# with_usb.net
KiCad netlist of a schematic drawn in EAGLE
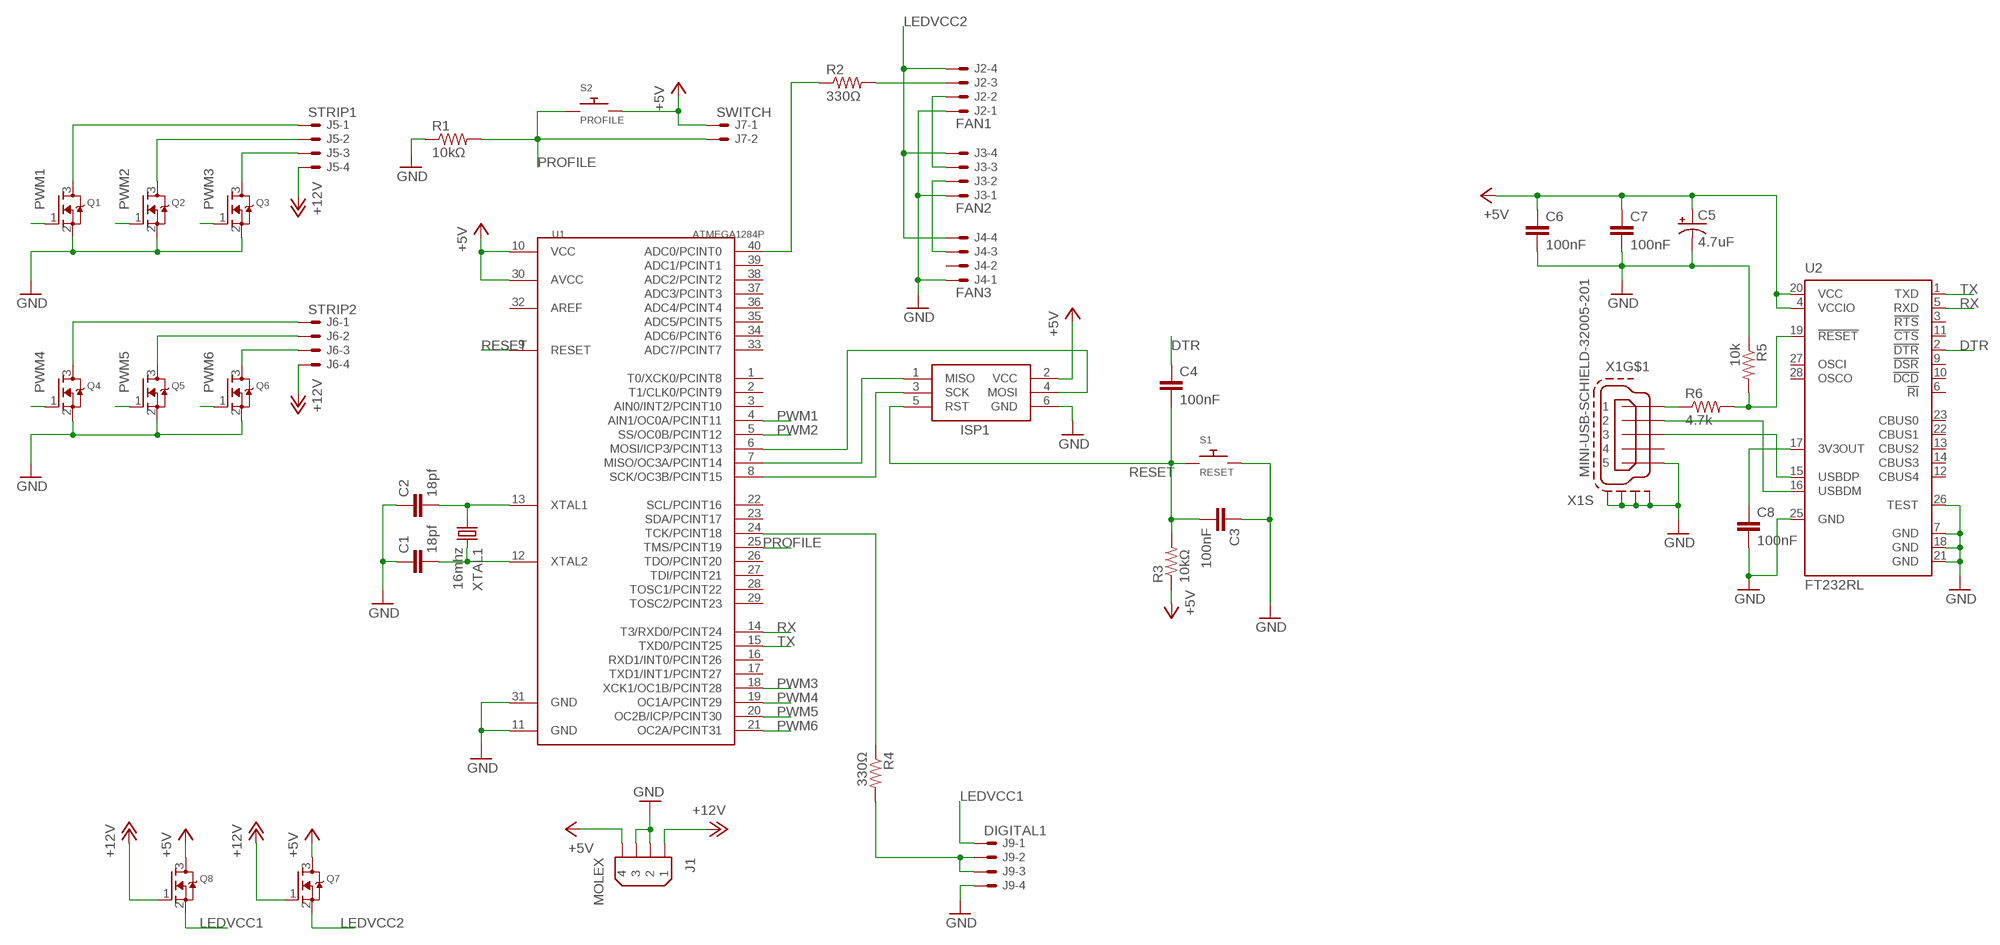
[diagram p0: schematic, sheet 1]

(export (version "E")
  (design (tool "Eeschema 10.0.6"))
  (components
    (comp (ref "C1")
      (value "18pf")
      (footprint "eagle-import:C0805")
      (libsource (lib "eagle-import") (part "C"))
    )
    (comp (ref "C2")
      (value "18pf")
      (footprint "eagle-import:C0805")
      (libsource (lib "eagle-import") (part "C"))
    )
    (comp (ref "C3")
      (value "100nF")
      (footprint "eagle-import:C0805")
      (libsource (lib "eagle-import") (part "C-EUC0805"))
    )
    (comp (ref "C4")
      (value "100nF")
      (footprint "eagle-import:C0805")
      (libsource (lib "eagle-import") (part "C-EUC0805"))
    )
    (comp (ref "C5")
      (value "4.7uF")
      (footprint "eagle-import:153CLV-0505")
      (libsource (lib "eagle-import") (part "CPOL-US153CLV-0505"))
    )
    (comp (ref "C6")
      (value "100nF")
      (footprint "eagle-import:C0805")
      (libsource (lib "eagle-import") (part "resistor_348_C-EUC0805"))
    )
    (comp (ref "C7")
      (value "100nF")
      (footprint "eagle-import:C0805")
      (libsource (lib "eagle-import") (part "resistor_348_C-EUC0805"))
    )
    (comp (ref "C8")
      (value "100nF")
      (footprint "eagle-import:C0805")
      (libsource (lib "eagle-import") (part "resistor_348_C-EUC0805"))
    )
    (comp (ref "ISP1")
      (value "AVRISP-6")
      (footprint "eagle-import:AVRISP")
      (libsource (lib "eagle-import") (part "AVRISP-6"))
    )
    (comp (ref "J1")
      (value "MOLEX")
      (footprint "eagle-import:9090-4R")
      (libsource (lib "eagle-import") (part "9090-4R"))
    )
    (comp (ref "J2")
      (value "FAN1")
      (footprint "eagle-import:22-23-2041")
      (fields (field (name "MF") "MOLEX") (field (name "MPN") "22-23-2041"))
      (libsource (lib "eagle-import") (part "22-23-2041"))
    )
    (comp (ref "J3")
      (value "FAN2")
      (footprint "eagle-import:22-23-2041")
      (fields (field (name "MF") "MOLEX") (field (name "MPN") "22-23-2041"))
      (libsource (lib "eagle-import") (part "22-23-2041"))
    )
    (comp (ref "J4")
      (value "FAN3")
      (footprint "eagle-import:22-23-2041")
      (fields (field (name "MF") "MOLEX") (field (name "MPN") "22-23-2041"))
      (libsource (lib "eagle-import") (part "22-23-2041"))
    )
    (comp (ref "J5")
      (value "STRIP1")
      (footprint "eagle-import:22-23-2041")
      (fields (field (name "MF") "MOLEX") (field (name "MPN") "22-23-2041"))
      (libsource (lib "eagle-import") (part "22-23-2041"))
    )
    (comp (ref "J6")
      (value "STRIP2")
      (footprint "eagle-import:22-23-2041")
      (fields (field (name "MF") "MOLEX") (field (name "MPN") "22-23-2041"))
      (libsource (lib "eagle-import") (part "22-23-2041"))
    )
    (comp (ref "J7")
      (value "SWITCH")
      (footprint "eagle-import:22-23-2021")
      (fields (field (name "MF") "MOLEX") (field (name "MPN") "22-23-2021"))
      (libsource (lib "eagle-import") (part "22-23-2021"))
    )
    (comp (ref "J9")
      (value "DIGITAL1")
      (footprint "eagle-import:22-23-2041")
      (fields (field (name "MF") "MOLEX") (field (name "MPN") "22-23-2041"))
      (libsource (lib "eagle-import") (part "22-23-2041"))
    )
    (comp (ref "Q1")
      (value "MOSFET-NREFLOW")
      (footprint "eagle-import:SOT23")
      (libsource (lib "eagle-import") (part "MOSFET-NREFLOW"))
    )
    (comp (ref "Q2")
      (value "MOSFET-NREFLOW")
      (footprint "eagle-import:SOT23")
      (libsource (lib "eagle-import") (part "MOSFET-NREFLOW"))
    )
    (comp (ref "Q3")
      (value "MOSFET-NREFLOW")
      (footprint "eagle-import:SOT23")
      (libsource (lib "eagle-import") (part "MOSFET-NREFLOW"))
    )
    (comp (ref "Q4")
      (value "MOSFET-NREFLOW")
      (footprint "eagle-import:SOT23")
      (libsource (lib "eagle-import") (part "MOSFET-NREFLOW"))
    )
    (comp (ref "Q5")
      (value "MOSFET-NREFLOW")
      (footprint "eagle-import:SOT23")
      (libsource (lib "eagle-import") (part "MOSFET-NREFLOW"))
    )
    (comp (ref "Q6")
      (value "MOSFET-NREFLOW")
      (footprint "eagle-import:SOT23")
      (libsource (lib "eagle-import") (part "MOSFET-NREFLOW"))
    )
    (comp (ref "Q7")
      (value "MOSFET-NREFLOW")
      (footprint "eagle-import:SOT23")
      (libsource (lib "eagle-import") (part "MOSFET-NREFLOW"))
    )
    (comp (ref "Q8")
      (value "MOSFET-NREFLOW")
      (footprint "eagle-import:SOT23")
      (libsource (lib "eagle-import") (part "MOSFET-NREFLOW"))
    )
    (comp (ref "R1")
      (value "10kΩ")
      (footprint "eagle-import:M0805")
      (libsource (lib "eagle-import") (part "R-US_M0805"))
    )
    (comp (ref "R2")
      (value "330Ω")
      (footprint "eagle-import:M0805")
      (libsource (lib "eagle-import") (part "R-US_M0805"))
    )
    (comp (ref "R3")
      (value "10kΩ")
      (footprint "eagle-import:M0805")
      (libsource (lib "eagle-import") (part "R-US_M0805"))
    )
    (comp (ref "R4")
      (value "330Ω")
      (footprint "eagle-import:M0805")
      (libsource (lib "eagle-import") (part "R-US_M0805"))
    )
    (comp (ref "R5")
      (value "10k")
      (footprint "eagle-import:R0805")
      (libsource (lib "eagle-import") (part "resistor_348_R-US_R0805"))
    )
    (comp (ref "R6")
      (value "4.7k")
      (footprint "eagle-import:R0805")
      (libsource (lib "eagle-import") (part "resistor_348_R-US_R0805"))
    )
    (comp (ref "S1")
      (value "RESET")
      (footprint "eagle-import:B3F-1000")
      (libsource (lib "eagle-import") (part "BUTTON"))
    )
    (comp (ref "S2")
      (value "PROFILE")
      (footprint "eagle-import:B3F-1000")
      (libsource (lib "eagle-import") (part "BUTTON"))
    )
    (comp (ref "U1")
      (value "ATMEGA1284P")
      (footprint "eagle-import:DIL40")
      (libsource (lib "eagle-import") (part "MEGA1284P"))
    )
    (comp (ref "U2")
      (value "FT232RL")
      (footprint "eagle-import:SSOP28")
      (libsource (lib "eagle-import") (part "FT232RL"))
    )
    (comp (ref "X1")
      (value "MINI-USB-SCHIELD-32005-201")
      (footprint "eagle-import:32005-201")
      (libsource (lib "eagle-import") (part "MINI-USB-SCHIELD-32005-201"))
    )
    (comp (ref "XTAL1")
      (value "16mhz")
      (footprint "eagle-import:HC49U-V")
      (libsource (lib "eagle-import") (part "CRYSTALHC49U-V"))
    )
  )
  (nets
    (net (code "1") (name "+5V") (class "Default")
      (node (ref "C5") (pin "+") (pinfunction "+_+") (pintype "passive"))
      (node (ref "C6") (pin "1") (pinfunction "1_1") (pintype "passive"))
      (node (ref "C7") (pin "1") (pinfunction "1_1") (pintype "passive"))
      (node (ref "ISP1") (pin "2") (pinfunction "VCC_2") (pintype "power_in"))
      (node (ref "J1") (pin "4") (pinfunction "4_4") (pintype "passive"))
      (node (ref "J7") (pin "1") (pinfunction "S_1") (pintype "passive"))
      (node (ref "Q7") (pin "3") (pinfunction "D_3") (pintype "bidirectional"))
      (node (ref "Q8") (pin "3") (pinfunction "D_3") (pintype "bidirectional"))
      (node (ref "R3") (pin "1") (pinfunction "1_1") (pintype "passive"))
      (node (ref "S2") (pin "3") (pinfunction "P$2_3") (pintype "passive"))
      (node (ref "S2") (pin "4") (pinfunction "P$2_4") (pintype "passive"))
      (node (ref "U1") (pin "10") (pinfunction "VCC_10") (pintype "bidirectional"))
      (node (ref "U1") (pin "30") (pinfunction "AVCC_30") (pintype "bidirectional"))
      (node (ref "U2") (pin "20") (pinfunction "VCC_20") (pintype "power_in"))
      (node (ref "U2") (pin "4") (pinfunction "VCCIO_4") (pintype "power_in"))
    )
    (net (code "2") (name "+12V") (class "Default")
      (node (ref "J1") (pin "1") (pinfunction "1_1") (pintype "passive"))
      (node (ref "J5") (pin "4") (pinfunction "S_4") (pintype "passive"))
      (node (ref "J6") (pin "4") (pinfunction "S_4") (pintype "passive"))
      (node (ref "Q7") (pin "1") (pinfunction "G_1") (pintype "bidirectional"))
      (node (ref "Q8") (pin "1") (pinfunction "G_1") (pintype "bidirectional"))
    )
    (net (code "3") (name "/DTR") (class "Default")
      (node (ref "C4") (pin "1") (pinfunction "1_1") (pintype "passive"))
      (node (ref "U2") (pin "2") (pinfunction "~{DTR}_2") (pintype "output"))
    )
    (net (code "4") (name "/LEDVCC1") (class "Default")
      (node (ref "J9") (pin "1") (pinfunction "S_1") (pintype "passive"))
      (node (ref "Q8") (pin "2") (pinfunction "S_2") (pintype "bidirectional"))
    )
    (net (code "5") (name "/LEDVCC2") (class "Default")
      (node (ref "J2") (pin "4") (pinfunction "S_4") (pintype "passive"))
      (node (ref "J3") (pin "4") (pinfunction "S_4") (pintype "passive"))
      (node (ref "J4") (pin "4") (pinfunction "S_4") (pintype "passive"))
      (node (ref "Q7") (pin "2") (pinfunction "S_2") (pintype "bidirectional"))
    )
    (net (code "6") (name "/PROFILE") (class "Default")
      (node (ref "J7") (pin "2") (pinfunction "S_2") (pintype "passive"))
      (node (ref "R1") (pin "2") (pinfunction "2_2") (pintype "passive"))
      (node (ref "S2") (pin "1") (pinfunction "P$1_1") (pintype "passive"))
      (node (ref "S2") (pin "2") (pinfunction "P$1_2") (pintype "passive"))
      (node (ref "U1") (pin "25") (pinfunction "TMS/PCINT19_25") (pintype "bidirectional"))
    )
    (net (code "7") (name "/PWM1") (class "Default")
      (node (ref "Q1") (pin "1") (pinfunction "G_1") (pintype "bidirectional"))
      (node (ref "U1") (pin "4") (pinfunction "AIN1/OC0A/PCINT11_4") (pintype "bidirectional"))
    )
    (net (code "8") (name "/PWM2") (class "Default")
      (node (ref "Q2") (pin "1") (pinfunction "G_1") (pintype "bidirectional"))
      (node (ref "U1") (pin "5") (pinfunction "SS/OC0B/PCINT12_5") (pintype "bidirectional"))
    )
    (net (code "9") (name "/PWM3") (class "Default")
      (node (ref "Q3") (pin "1") (pinfunction "G_1") (pintype "bidirectional"))
      (node (ref "U1") (pin "18") (pinfunction "XCK1/OC1B/PCINT28_18") (pintype "bidirectional"))
    )
    (net (code "10") (name "/PWM4") (class "Default")
      (node (ref "Q4") (pin "1") (pinfunction "G_1") (pintype "bidirectional"))
      (node (ref "U1") (pin "19") (pinfunction "OC1A/PCINT29_19") (pintype "bidirectional"))
    )
    (net (code "11") (name "/PWM5") (class "Default")
      (node (ref "Q5") (pin "1") (pinfunction "G_1") (pintype "bidirectional"))
      (node (ref "U1") (pin "20") (pinfunction "OC2B/ICP/PCINT30_20") (pintype "bidirectional"))
    )
    (net (code "12") (name "/PWM6") (class "Default")
      (node (ref "Q6") (pin "1") (pinfunction "G_1") (pintype "bidirectional"))
      (node (ref "U1") (pin "21") (pinfunction "OC2A/PCINT31_21") (pintype "bidirectional"))
    )
    (net (code "13") (name "/RESET") (class "Default")
      (node (ref "C3") (pin "2") (pinfunction "2_2") (pintype "passive"))
      (node (ref "C4") (pin "2") (pinfunction "2_2") (pintype "passive"))
      (node (ref "ISP1") (pin "5") (pinfunction "RST_5") (pintype "output"))
      (node (ref "R3") (pin "2") (pinfunction "2_2") (pintype "passive"))
      (node (ref "S1") (pin "1") (pinfunction "P$1_1") (pintype "passive"))
      (node (ref "S1") (pin "2") (pinfunction "P$1_2") (pintype "passive"))
      (node (ref "U1") (pin "9") (pinfunction "RESET_9") (pintype "bidirectional"))
    )
    (net (code "14") (name "/RX") (class "Default")
      (node (ref "U1") (pin "14") (pinfunction "T3/RXD0/PCINT24_14") (pintype "bidirectional"))
      (node (ref "U2") (pin "5") (pinfunction "RXD_5") (pintype "input"))
    )
    (net (code "15") (name "/TX") (class "Default")
      (node (ref "U1") (pin "15") (pinfunction "TXD0/PCINT25_15") (pintype "bidirectional"))
      (node (ref "U2") (pin "1") (pinfunction "TXD_1") (pintype "output"))
    )
    (net (code "16") (name "GND") (class "Default")
      (node (ref "C1") (pin "1") (pinfunction "1_1") (pintype "passive"))
      (node (ref "C2") (pin "1") (pinfunction "1_1") (pintype "passive"))
      (node (ref "C3") (pin "1") (pinfunction "1_1") (pintype "passive"))
      (node (ref "C5") (pin "-") (pinfunction "-_-") (pintype "passive"))
      (node (ref "C6") (pin "2") (pinfunction "2_2") (pintype "passive"))
      (node (ref "C7") (pin "2") (pinfunction "2_2") (pintype "passive"))
      (node (ref "C8") (pin "2") (pinfunction "2_2") (pintype "passive"))
      (node (ref "ISP1") (pin "6") (pinfunction "GND_6") (pintype "power_in"))
      (node (ref "J1") (pin "2") (pinfunction "2_2") (pintype "passive"))
      (node (ref "J1") (pin "3") (pinfunction "3_3") (pintype "passive"))
      (node (ref "J2") (pin "1") (pinfunction "S_1") (pintype "passive"))
      (node (ref "J3") (pin "1") (pinfunction "S_1") (pintype "passive"))
      (node (ref "J4") (pin "1") (pinfunction "S_1") (pintype "passive"))
      (node (ref "J9") (pin "4") (pinfunction "S_4") (pintype "passive"))
      (node (ref "Q1") (pin "2") (pinfunction "S_2") (pintype "bidirectional"))
      (node (ref "Q2") (pin "2") (pinfunction "S_2") (pintype "bidirectional"))
      (node (ref "Q3") (pin "2") (pinfunction "S_2") (pintype "bidirectional"))
      (node (ref "Q4") (pin "2") (pinfunction "S_2") (pintype "bidirectional"))
      (node (ref "Q5") (pin "2") (pinfunction "S_2") (pintype "bidirectional"))
      (node (ref "Q6") (pin "2") (pinfunction "S_2") (pintype "bidirectional"))
      (node (ref "R1") (pin "1") (pinfunction "1_1") (pintype "passive"))
      (node (ref "R5") (pin "1") (pinfunction "1_1") (pintype "passive"))
      (node (ref "S1") (pin "3") (pinfunction "P$2_3") (pintype "passive"))
      (node (ref "S1") (pin "4") (pinfunction "P$2_4") (pintype "passive"))
      (node (ref "U1") (pin "11") (pinfunction "GND_11") (pintype "bidirectional"))
      (node (ref "U1") (pin "31") (pinfunction "GND_31") (pintype "bidirectional"))
      (node (ref "U2") (pin "18") (pinfunction "GND_18") (pintype "power_in"))
      (node (ref "U2") (pin "21") (pinfunction "GND_21") (pintype "power_in"))
      (node (ref "U2") (pin "25") (pinfunction "GND_25") (pintype "power_in"))
      (node (ref "U2") (pin "26") (pinfunction "TEST_26") (pintype "input"))
      (node (ref "U2") (pin "7") (pinfunction "GND_7") (pintype "power_in"))
      (node (ref "X1") (pin "5") (pinfunction "5_5") (pintype "passive"))
      (node (ref "X1") (pin "M1") (pinfunction "S1_M1") (pintype "passive"))
      (node (ref "X1") (pin "M2") (pinfunction "S2_M2") (pintype "passive"))
      (node (ref "X1") (pin "M3") (pinfunction "S3_M3") (pintype "passive"))
      (node (ref "X1") (pin "M4") (pinfunction "S4_M4") (pintype "passive"))
    )
    (net (code "17") (name "Net-(ISP1-MISO)") (class "Default")
      (node (ref "ISP1") (pin "1") (pinfunction "MISO_1") (pintype "input"))
      (node (ref "U1") (pin "7") (pinfunction "MISO/OC3A/PCINT14_7") (pintype "bidirectional"))
    )
    (net (code "18") (name "Net-(ISP1-MOSI)") (class "Default")
      (node (ref "ISP1") (pin "4") (pinfunction "MOSI_4") (pintype "output"))
      (node (ref "U1") (pin "6") (pinfunction "MOSI/ICP3/PCINT13_6") (pintype "bidirectional"))
    )
    (net (code "19") (name "Net-(ISP1-SCK)") (class "Default")
      (node (ref "ISP1") (pin "3") (pinfunction "SCK_3") (pintype "output"))
      (node (ref "U1") (pin "8") (pinfunction "SCK/OC3B/PCINT15_8") (pintype "bidirectional"))
    )
    (net (code "20") (name "Net-(J2B-S)") (class "Default")
      (node (ref "J2") (pin "2") (pinfunction "S_2") (pintype "passive"))
      (node (ref "J3") (pin "3") (pinfunction "S_3") (pintype "passive"))
    )
    (net (code "21") (name "Net-(J2C-S)") (class "Default")
      (node (ref "J2") (pin "3") (pinfunction "S_3") (pintype "passive"))
      (node (ref "R2") (pin "2") (pinfunction "2_2") (pintype "passive"))
    )
    (net (code "22") (name "Net-(J3B-S)") (class "Default")
      (node (ref "J3") (pin "2") (pinfunction "S_2") (pintype "passive"))
      (node (ref "J4") (pin "3") (pinfunction "S_3") (pintype "passive"))
    )
    (net (code "23") (name "Net-(J5A-S)") (class "Default")
      (node (ref "J5") (pin "1") (pinfunction "S_1") (pintype "passive"))
      (node (ref "Q1") (pin "3") (pinfunction "D_3") (pintype "bidirectional"))
    )
    (net (code "24") (name "Net-(J5B-S)") (class "Default")
      (node (ref "J5") (pin "2") (pinfunction "S_2") (pintype "passive"))
      (node (ref "Q2") (pin "3") (pinfunction "D_3") (pintype "bidirectional"))
    )
    (net (code "25") (name "Net-(J5C-S)") (class "Default")
      (node (ref "J5") (pin "3") (pinfunction "S_3") (pintype "passive"))
      (node (ref "Q3") (pin "3") (pinfunction "D_3") (pintype "bidirectional"))
    )
    (net (code "26") (name "Net-(J6A-S)") (class "Default")
      (node (ref "J6") (pin "1") (pinfunction "S_1") (pintype "passive"))
      (node (ref "Q4") (pin "3") (pinfunction "D_3") (pintype "bidirectional"))
    )
    (net (code "27") (name "Net-(J6B-S)") (class "Default")
      (node (ref "J6") (pin "2") (pinfunction "S_2") (pintype "passive"))
      (node (ref "Q5") (pin "3") (pinfunction "D_3") (pintype "bidirectional"))
    )
    (net (code "28") (name "Net-(J6C-S)") (class "Default")
      (node (ref "J6") (pin "3") (pinfunction "S_3") (pintype "passive"))
      (node (ref "Q6") (pin "3") (pinfunction "D_3") (pintype "bidirectional"))
    )
    (net (code "29") (name "Net-(J9B-S)") (class "Default")
      (node (ref "J9") (pin "2") (pinfunction "S_2") (pintype "passive"))
      (node (ref "J9") (pin "3") (pinfunction "S_3") (pintype "passive"))
      (node (ref "R4") (pin "2") (pinfunction "2_2") (pintype "passive"))
    )
    (net (code "30") (name "Net-(R6-Pad1)") (class "Default")
      (node (ref "R6") (pin "1") (pinfunction "1_1") (pintype "passive"))
      (node (ref "X1") (pin "1") (pinfunction "1_1") (pintype "passive"))
    )
    (net (code "31") (name "Net-(U1-ADC0{slash}PCINT0)") (class "Default")
      (node (ref "R2") (pin "1") (pinfunction "1_1") (pintype "passive"))
      (node (ref "U1") (pin "40") (pinfunction "ADC0/PCINT0_40") (pintype "bidirectional"))
    )
    (net (code "32") (name "Net-(U1-TCK{slash}PCINT18)") (class "Default")
      (node (ref "R4") (pin "1") (pinfunction "1_1") (pintype "passive"))
      (node (ref "U1") (pin "24") (pinfunction "TCK/PCINT18_24") (pintype "bidirectional"))
    )
    (net (code "33") (name "Net-(U1-XTAL1)") (class "Default")
      (node (ref "C2") (pin "2") (pinfunction "2_2") (pintype "passive"))
      (node (ref "U1") (pin "13") (pinfunction "XTAL1_13") (pintype "bidirectional"))
      (node (ref "XTAL1") (pin "1") (pinfunction "1_1") (pintype "passive"))
    )
    (net (code "34") (name "Net-(U1-XTAL2)") (class "Default")
      (node (ref "C1") (pin "2") (pinfunction "2_2") (pintype "passive"))
      (node (ref "U1") (pin "12") (pinfunction "XTAL2_12") (pintype "bidirectional"))
      (node (ref "XTAL1") (pin "2") (pinfunction "2_2") (pintype "passive"))
    )
    (net (code "35") (name "Net-(U2-3V3OUT)") (class "Default")
      (node (ref "C8") (pin "1") (pinfunction "1_1") (pintype "passive"))
      (node (ref "U2") (pin "17") (pinfunction "3V3OUT_17") (pintype "output"))
    )
    (net (code "36") (name "Net-(U2-USBDM)") (class "Default")
      (node (ref "U2") (pin "16") (pinfunction "USBDM_16") (pintype "bidirectional"))
      (node (ref "X1") (pin "2") (pinfunction "2_2") (pintype "passive"))
    )
    (net (code "37") (name "Net-(U2-USBDP)") (class "Default")
      (node (ref "U2") (pin "15") (pinfunction "USBDP_15") (pintype "bidirectional"))
      (node (ref "X1") (pin "3") (pinfunction "3_3") (pintype "passive"))
    )
    (net (code "38") (name "Net-(U2-~{RESET})") (class "Default")
      (node (ref "R5") (pin "2") (pinfunction "2_2") (pintype "passive"))
      (node (ref "R6") (pin "2") (pinfunction "2_2") (pintype "passive"))
      (node (ref "U2") (pin "19") (pinfunction "~{RESET}_19") (pintype "input"))
    )
    (net (code "39") (name "unconnected-(J4B-S-Pad2)") (class "Default")
      (node (ref "J4") (pin "2") (pinfunction "S_2") (pintype "passive"))
    )
    (net (code "40") (name "unconnected-(U1-ADC1{slash}PCINT1-Pad39)") (class "Default")
      (node (ref "U1") (pin "39") (pinfunction "ADC1/PCINT1_39") (pintype "bidirectional"))
    )
    (net (code "41") (name "unconnected-(U1-ADC2{slash}PCINT2-Pad38)") (class "Default")
      (node (ref "U1") (pin "38") (pinfunction "ADC2/PCINT2_38") (pintype "bidirectional"))
    )
    (net (code "42") (name "unconnected-(U1-ADC3{slash}PCINT3-Pad37)") (class "Default")
      (node (ref "U1") (pin "37") (pinfunction "ADC3/PCINT3_37") (pintype "bidirectional"))
    )
    (net (code "43") (name "unconnected-(U1-ADC4{slash}PCINT4-Pad36)") (class "Default")
      (node (ref "U1") (pin "36") (pinfunction "ADC4/PCINT4_36") (pintype "bidirectional"))
    )
    (net (code "44") (name "unconnected-(U1-ADC5{slash}PCINT5-Pad35)") (class "Default")
      (node (ref "U1") (pin "35") (pinfunction "ADC5/PCINT5_35") (pintype "bidirectional"))
    )
    (net (code "45") (name "unconnected-(U1-ADC6{slash}PCINT6-Pad34)") (class "Default")
      (node (ref "U1") (pin "34") (pinfunction "ADC6/PCINT6_34") (pintype "bidirectional"))
    )
    (net (code "46") (name "unconnected-(U1-ADC7{slash}PCINT7-Pad33)") (class "Default")
      (node (ref "U1") (pin "33") (pinfunction "ADC7/PCINT7_33") (pintype "bidirectional"))
    )
    (net (code "47") (name "unconnected-(U1-AIN0{slash}INT2{slash}PCINT10-Pad3)") (class "Default")
      (node (ref "U1") (pin "3") (pinfunction "AIN0/INT2/PCINT10_3") (pintype "bidirectional"))
    )
    (net (code "48") (name "unconnected-(U1-AREF-Pad32)") (class "Default")
      (node (ref "U1") (pin "32") (pinfunction "AREF_32") (pintype "bidirectional"))
    )
    (net (code "49") (name "unconnected-(U1-RXD1{slash}INT0{slash}PCINT26-Pad16)") (class "Default")
      (node (ref "U1") (pin "16") (pinfunction "RXD1/INT0/PCINT26_16") (pintype "bidirectional"))
    )
    (net (code "50") (name "unconnected-(U1-SCL{slash}PCINT16-Pad22)") (class "Default")
      (node (ref "U1") (pin "22") (pinfunction "SCL/PCINT16_22") (pintype "bidirectional"))
    )
    (net (code "51") (name "unconnected-(U1-SDA{slash}PCINT17-Pad23)") (class "Default")
      (node (ref "U1") (pin "23") (pinfunction "SDA/PCINT17_23") (pintype "bidirectional"))
    )
    (net (code "52") (name "unconnected-(U1-T0{slash}XCK0{slash}PCINT8-Pad1)") (class "Default")
      (node (ref "U1") (pin "1") (pinfunction "T0/XCK0/PCINT8_1") (pintype "bidirectional"))
    )
    (net (code "53") (name "unconnected-(U1-T1{slash}CLK0{slash}PCINT9-Pad2)") (class "Default")
      (node (ref "U1") (pin "2") (pinfunction "T1/CLK0/PCINT9_2") (pintype "bidirectional"))
    )
    (net (code "54") (name "unconnected-(U1-TDI{slash}PCINT21-Pad27)") (class "Default")
      (node (ref "U1") (pin "27") (pinfunction "TDI/PCINT21_27") (pintype "bidirectional"))
    )
    (net (code "55") (name "unconnected-(U1-TDO{slash}PCINT20-Pad26)") (class "Default")
      (node (ref "U1") (pin "26") (pinfunction "TDO/PCINT20_26") (pintype "bidirectional"))
    )
    (net (code "56") (name "unconnected-(U1-TOSC1{slash}PCINT22-Pad28)") (class "Default")
      (node (ref "U1") (pin "28") (pinfunction "TOSC1/PCINT22_28") (pintype "bidirectional"))
    )
    (net (code "57") (name "unconnected-(U1-TOSC2{slash}PCINT23-Pad29)") (class "Default")
      (node (ref "U1") (pin "29") (pinfunction "TOSC2/PCINT23_29") (pintype "bidirectional"))
    )
    (net (code "58") (name "unconnected-(U1-TXD1{slash}INT1{slash}PCINT27-Pad17)") (class "Default")
      (node (ref "U1") (pin "17") (pinfunction "TXD1/INT1/PCINT27_17") (pintype "bidirectional"))
    )
    (net (code "59") (name "unconnected-(U2-CBUS0-Pad23)") (class "Default")
      (node (ref "U2") (pin "23") (pinfunction "CBUS0_23") (pintype "bidirectional"))
    )
    (net (code "60") (name "unconnected-(U2-CBUS1-Pad22)") (class "Default")
      (node (ref "U2") (pin "22") (pinfunction "CBUS1_22") (pintype "bidirectional"))
    )
    (net (code "61") (name "unconnected-(U2-CBUS2-Pad13)") (class "Default")
      (node (ref "U2") (pin "13") (pinfunction "CBUS2_13") (pintype "bidirectional"))
    )
    (net (code "62") (name "unconnected-(U2-CBUS3-Pad14)") (class "Default")
      (node (ref "U2") (pin "14") (pinfunction "CBUS3_14") (pintype "bidirectional"))
    )
    (net (code "63") (name "unconnected-(U2-CBUS4-Pad12)") (class "Default")
      (node (ref "U2") (pin "12") (pinfunction "CBUS4_12") (pintype "bidirectional"))
    )
    (net (code "64") (name "unconnected-(U2-OSCI-Pad27)") (class "Default")
      (node (ref "U2") (pin "27") (pinfunction "OSCI_27") (pintype "input"))
    )
    (net (code "65") (name "unconnected-(U2-OSCO-Pad28)") (class "Default")
      (node (ref "U2") (pin "28") (pinfunction "OSCO_28") (pintype "output"))
    )
    (net (code "66") (name "unconnected-(U2-~{CTS}-Pad11)") (class "Default")
      (node (ref "U2") (pin "11") (pinfunction "~{CTS}_11") (pintype "input"))
    )
    (net (code "67") (name "unconnected-(U2-~{DCD}-Pad10)") (class "Default")
      (node (ref "U2") (pin "10") (pinfunction "~{DCD}_10") (pintype "input"))
    )
    (net (code "68") (name "unconnected-(U2-~{DSR}-Pad9)") (class "Default")
      (node (ref "U2") (pin "9") (pinfunction "~{DSR}_9") (pintype "input"))
    )
    (net (code "69") (name "unconnected-(U2-~{RI}-Pad6)") (class "Default")
      (node (ref "U2") (pin "6") (pinfunction "~{RI}_6") (pintype "input"))
    )
    (net (code "70") (name "unconnected-(U2-~{RTS}-Pad3)") (class "Default")
      (node (ref "U2") (pin "3") (pinfunction "~{RTS}_3") (pintype "output"))
    )
    (net (code "71") (name "unconnected-(X1-Pad4)") (class "Default")
      (node (ref "X1") (pin "4") (pinfunction "4_4") (pintype "passive"))
    )
  )
)
